# box_opener.net
KiCad netlist of a schematic drawn in EAGLE
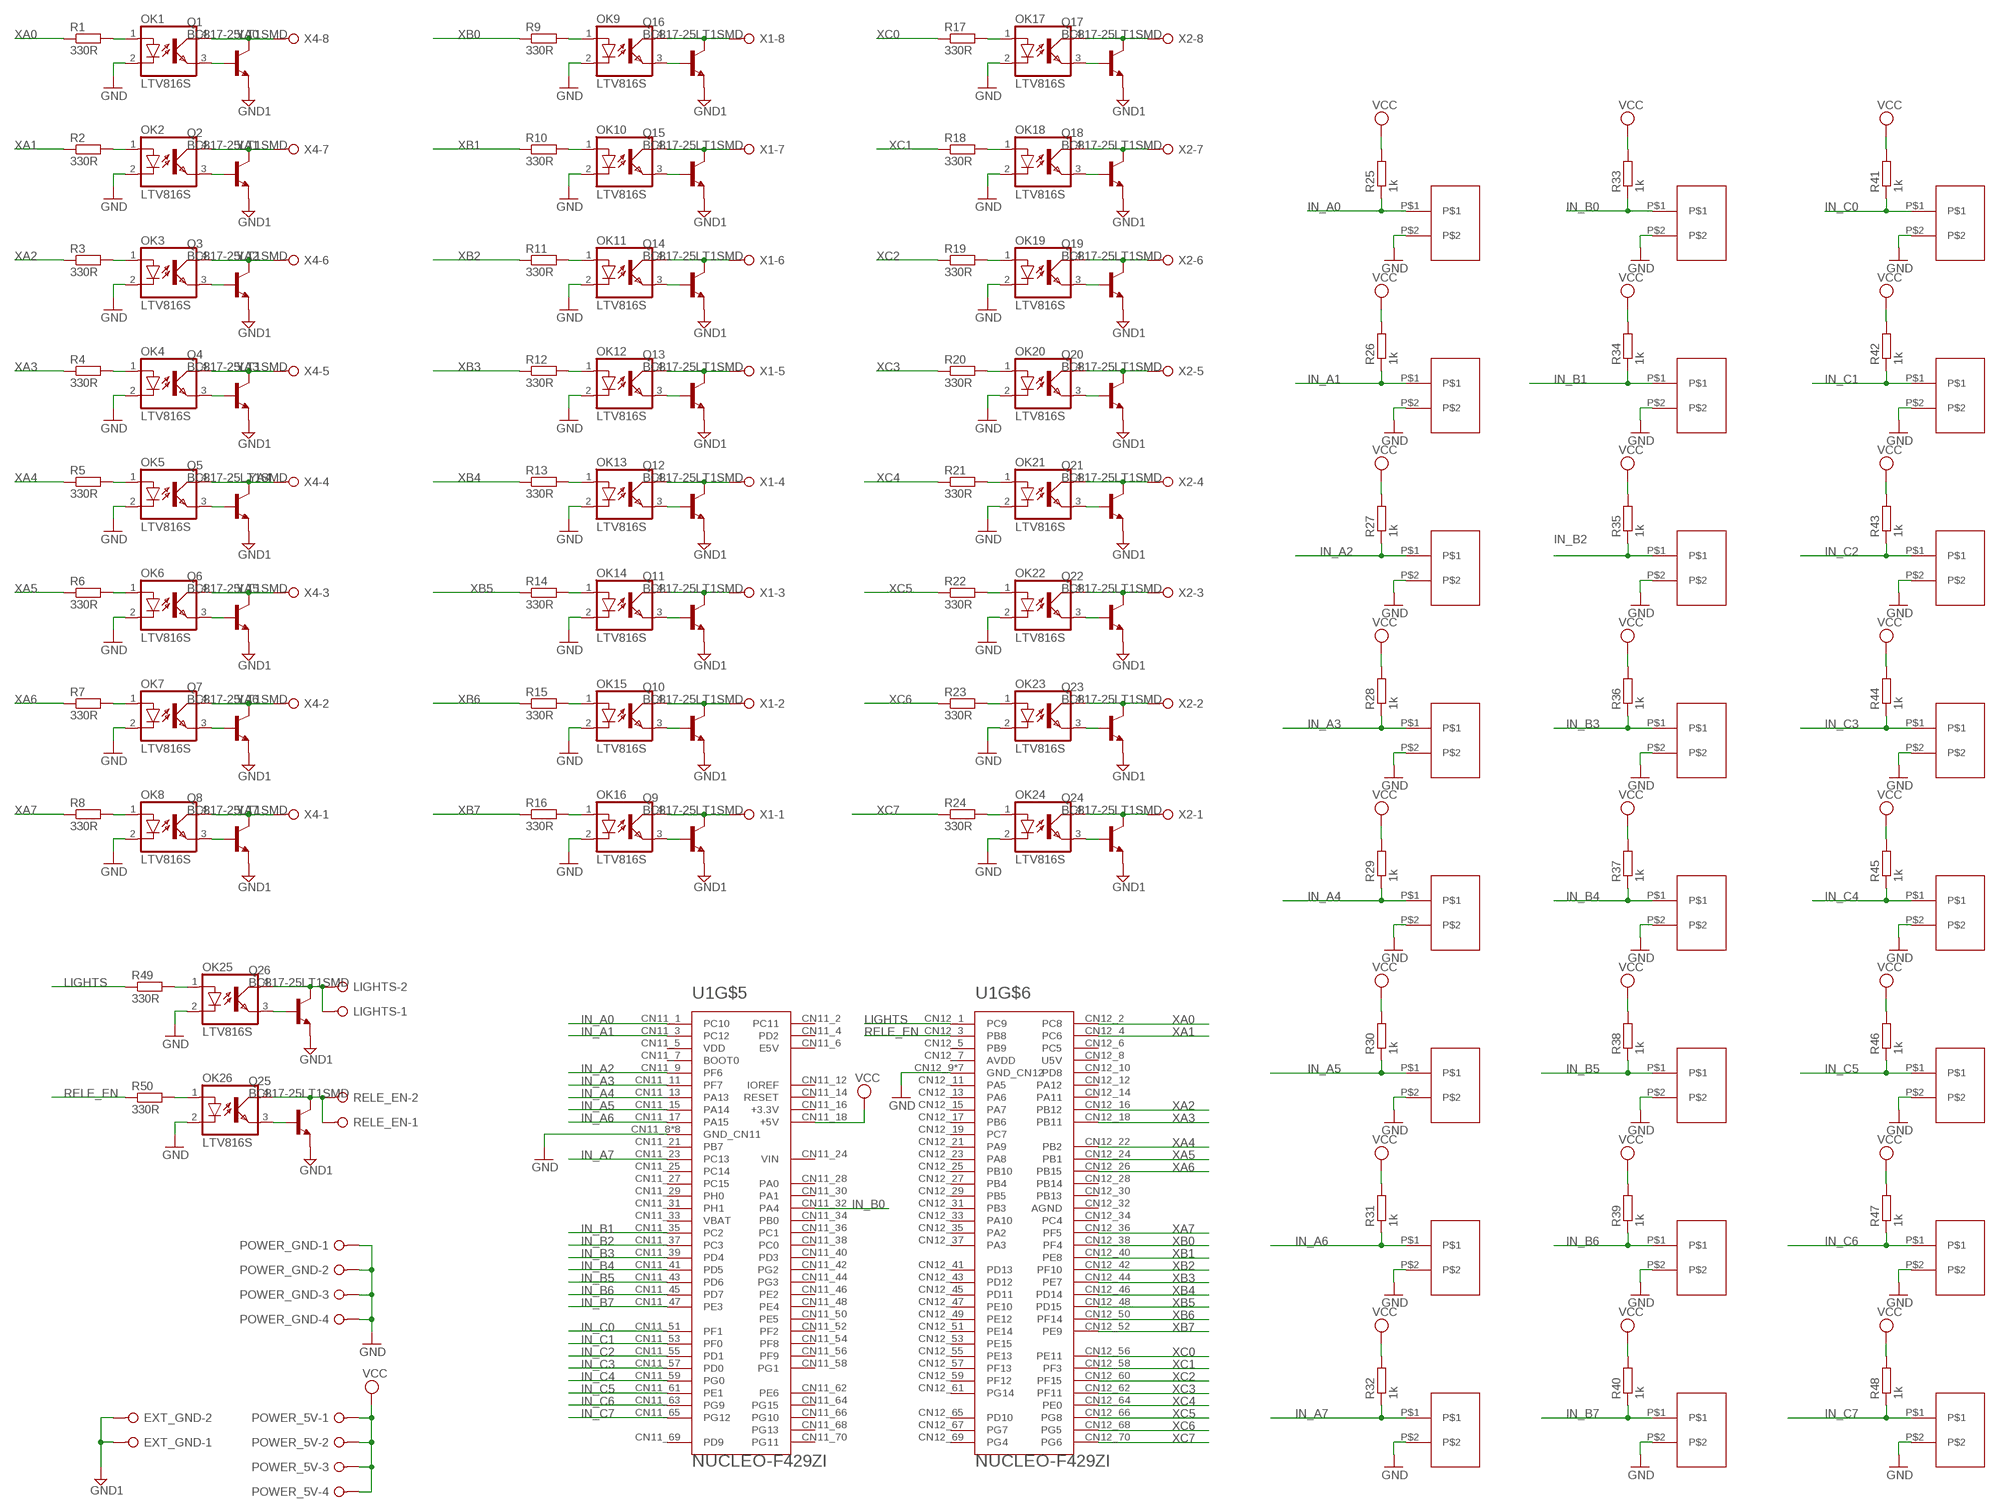
[diagram p0: schematic, sheet 1]

(export (version "E")
  (design (tool "Eeschema 10.0.6"))
  (components
    (comp (ref "EXT_GND")
      (value "W237-02P")
      (footprint "eagle-import:W237-132")
      (libsource (lib "eagle-import") (part "W237-02P"))
    )
    (comp (ref "LIGHTS")
      (value "W237-02P")
      (footprint "eagle-import:W237-132")
      (libsource (lib "eagle-import") (part "W237-02P"))
    )
    (comp (ref "OK1")
      (value "LTV816S")
      (footprint "eagle-import:DIL4-SMD")
      (libsource (lib "eagle-import") (part "LTV816S"))
    )
    (comp (ref "OK2")
      (value "LTV816S")
      (footprint "eagle-import:DIL4-SMD")
      (libsource (lib "eagle-import") (part "LTV816S"))
    )
    (comp (ref "OK3")
      (value "LTV816S")
      (footprint "eagle-import:DIL4-SMD")
      (libsource (lib "eagle-import") (part "LTV816S"))
    )
    (comp (ref "OK4")
      (value "LTV816S")
      (footprint "eagle-import:DIL4-SMD")
      (libsource (lib "eagle-import") (part "LTV816S"))
    )
    (comp (ref "OK5")
      (value "LTV816S")
      (footprint "eagle-import:DIL4-SMD")
      (libsource (lib "eagle-import") (part "LTV816S"))
    )
    (comp (ref "OK6")
      (value "LTV816S")
      (footprint "eagle-import:DIL4-SMD")
      (libsource (lib "eagle-import") (part "LTV816S"))
    )
    (comp (ref "OK7")
      (value "LTV816S")
      (footprint "eagle-import:DIL4-SMD")
      (libsource (lib "eagle-import") (part "LTV816S"))
    )
    (comp (ref "OK8")
      (value "LTV816S")
      (footprint "eagle-import:DIL4-SMD")
      (libsource (lib "eagle-import") (part "LTV816S"))
    )
    (comp (ref "OK9")
      (value "LTV816S")
      (footprint "eagle-import:DIL4-SMD")
      (libsource (lib "eagle-import") (part "LTV816S"))
    )
    (comp (ref "OK10")
      (value "LTV816S")
      (footprint "eagle-import:DIL4-SMD")
      (libsource (lib "eagle-import") (part "LTV816S"))
    )
    (comp (ref "OK11")
      (value "LTV816S")
      (footprint "eagle-import:DIL4-SMD")
      (libsource (lib "eagle-import") (part "LTV816S"))
    )
    (comp (ref "OK12")
      (value "LTV816S")
      (footprint "eagle-import:DIL4-SMD")
      (libsource (lib "eagle-import") (part "LTV816S"))
    )
    (comp (ref "OK13")
      (value "LTV816S")
      (footprint "eagle-import:DIL4-SMD")
      (libsource (lib "eagle-import") (part "LTV816S"))
    )
    (comp (ref "OK14")
      (value "LTV816S")
      (footprint "eagle-import:DIL4-SMD")
      (libsource (lib "eagle-import") (part "LTV816S"))
    )
    (comp (ref "OK15")
      (value "LTV816S")
      (footprint "eagle-import:DIL4-SMD")
      (libsource (lib "eagle-import") (part "LTV816S"))
    )
    (comp (ref "OK16")
      (value "LTV816S")
      (footprint "eagle-import:DIL4-SMD")
      (libsource (lib "eagle-import") (part "LTV816S"))
    )
    (comp (ref "OK17")
      (value "LTV816S")
      (footprint "eagle-import:DIL4-SMD")
      (libsource (lib "eagle-import") (part "LTV816S"))
    )
    (comp (ref "OK18")
      (value "LTV816S")
      (footprint "eagle-import:DIL4-SMD")
      (libsource (lib "eagle-import") (part "LTV816S"))
    )
    (comp (ref "OK19")
      (value "LTV816S")
      (footprint "eagle-import:DIL4-SMD")
      (libsource (lib "eagle-import") (part "LTV816S"))
    )
    (comp (ref "OK20")
      (value "LTV816S")
      (footprint "eagle-import:DIL4-SMD")
      (libsource (lib "eagle-import") (part "LTV816S"))
    )
    (comp (ref "OK21")
      (value "LTV816S")
      (footprint "eagle-import:DIL4-SMD")
      (libsource (lib "eagle-import") (part "LTV816S"))
    )
    (comp (ref "OK22")
      (value "LTV816S")
      (footprint "eagle-import:DIL4-SMD")
      (libsource (lib "eagle-import") (part "LTV816S"))
    )
    (comp (ref "OK23")
      (value "LTV816S")
      (footprint "eagle-import:DIL4-SMD")
      (libsource (lib "eagle-import") (part "LTV816S"))
    )
    (comp (ref "OK24")
      (value "LTV816S")
      (footprint "eagle-import:DIL4-SMD")
      (libsource (lib "eagle-import") (part "LTV816S"))
    )
    (comp (ref "OK25")
      (value "LTV816S")
      (footprint "eagle-import:DIL4-SMD")
      (libsource (lib "eagle-import") (part "LTV816S"))
    )
    (comp (ref "OK26")
      (value "LTV816S")
      (footprint "eagle-import:DIL4-SMD")
      (libsource (lib "eagle-import") (part "LTV816S"))
    )
    (comp (ref "POWER_5V")
      (value "W237-04P")
      (footprint "eagle-import:W237-4P")
      (libsource (lib "eagle-import") (part "W237-04P"))
    )
    (comp (ref "POWER_GND")
      (value "W237-04P")
      (footprint "eagle-import:W237-4P")
      (libsource (lib "eagle-import") (part "W237-04P"))
    )
    (comp (ref "Q1")
      (value "BC817-25LT1SMD")
      (footprint "eagle-import:SOT23-BEC")
      (libsource (lib "eagle-import") (part "BC817SMD-25LT1"))
    )
    (comp (ref "Q2")
      (value "BC817-25LT1SMD")
      (footprint "eagle-import:SOT23-BEC")
      (libsource (lib "eagle-import") (part "BC817SMD-25LT1"))
    )
    (comp (ref "Q3")
      (value "BC817-25LT1SMD")
      (footprint "eagle-import:SOT23-BEC")
      (libsource (lib "eagle-import") (part "BC817SMD-25LT1"))
    )
    (comp (ref "Q4")
      (value "BC817-25LT1SMD")
      (footprint "eagle-import:SOT23-BEC")
      (libsource (lib "eagle-import") (part "BC817SMD-25LT1"))
    )
    (comp (ref "Q5")
      (value "BC817-25LT1SMD")
      (footprint "eagle-import:SOT23-BEC")
      (libsource (lib "eagle-import") (part "BC817SMD-25LT1"))
    )
    (comp (ref "Q6")
      (value "BC817-25LT1SMD")
      (footprint "eagle-import:SOT23-BEC")
      (libsource (lib "eagle-import") (part "BC817SMD-25LT1"))
    )
    (comp (ref "Q7")
      (value "BC817-25LT1SMD")
      (footprint "eagle-import:SOT23-BEC")
      (libsource (lib "eagle-import") (part "BC817SMD-25LT1"))
    )
    (comp (ref "Q8")
      (value "BC817-25LT1SMD")
      (footprint "eagle-import:SOT23-BEC")
      (libsource (lib "eagle-import") (part "BC817SMD-25LT1"))
    )
    (comp (ref "Q9")
      (value "BC817-25LT1SMD")
      (footprint "eagle-import:SOT23-BEC")
      (libsource (lib "eagle-import") (part "BC817SMD-25LT1"))
    )
    (comp (ref "Q10")
      (value "BC817-25LT1SMD")
      (footprint "eagle-import:SOT23-BEC")
      (libsource (lib "eagle-import") (part "BC817SMD-25LT1"))
    )
    (comp (ref "Q11")
      (value "BC817-25LT1SMD")
      (footprint "eagle-import:SOT23-BEC")
      (libsource (lib "eagle-import") (part "BC817SMD-25LT1"))
    )
    (comp (ref "Q12")
      (value "BC817-25LT1SMD")
      (footprint "eagle-import:SOT23-BEC")
      (libsource (lib "eagle-import") (part "BC817SMD-25LT1"))
    )
    (comp (ref "Q13")
      (value "BC817-25LT1SMD")
      (footprint "eagle-import:SOT23-BEC")
      (libsource (lib "eagle-import") (part "BC817SMD-25LT1"))
    )
    (comp (ref "Q14")
      (value "BC817-25LT1SMD")
      (footprint "eagle-import:SOT23-BEC")
      (libsource (lib "eagle-import") (part "BC817SMD-25LT1"))
    )
    (comp (ref "Q15")
      (value "BC817-25LT1SMD")
      (footprint "eagle-import:SOT23-BEC")
      (libsource (lib "eagle-import") (part "BC817SMD-25LT1"))
    )
    (comp (ref "Q16")
      (value "BC817-25LT1SMD")
      (footprint "eagle-import:SOT23-BEC")
      (libsource (lib "eagle-import") (part "BC817SMD-25LT1"))
    )
    (comp (ref "Q17")
      (value "BC817-25LT1SMD")
      (footprint "eagle-import:SOT23-BEC")
      (libsource (lib "eagle-import") (part "BC817SMD-25LT1"))
    )
    (comp (ref "Q18")
      (value "BC817-25LT1SMD")
      (footprint "eagle-import:SOT23-BEC")
      (libsource (lib "eagle-import") (part "BC817SMD-25LT1"))
    )
    (comp (ref "Q19")
      (value "BC817-25LT1SMD")
      (footprint "eagle-import:SOT23-BEC")
      (libsource (lib "eagle-import") (part "BC817SMD-25LT1"))
    )
    (comp (ref "Q20")
      (value "BC817-25LT1SMD")
      (footprint "eagle-import:SOT23-BEC")
      (libsource (lib "eagle-import") (part "BC817SMD-25LT1"))
    )
    (comp (ref "Q21")
      (value "BC817-25LT1SMD")
      (footprint "eagle-import:SOT23-BEC")
      (libsource (lib "eagle-import") (part "BC817SMD-25LT1"))
    )
    (comp (ref "Q22")
      (value "BC817-25LT1SMD")
      (footprint "eagle-import:SOT23-BEC")
      (libsource (lib "eagle-import") (part "BC817SMD-25LT1"))
    )
    (comp (ref "Q23")
      (value "BC817-25LT1SMD")
      (footprint "eagle-import:SOT23-BEC")
      (libsource (lib "eagle-import") (part "BC817SMD-25LT1"))
    )
    (comp (ref "Q24")
      (value "BC817-25LT1SMD")
      (footprint "eagle-import:SOT23-BEC")
      (libsource (lib "eagle-import") (part "BC817SMD-25LT1"))
    )
    (comp (ref "Q25")
      (value "BC817-25LT1SMD")
      (footprint "eagle-import:SOT23-BEC")
      (libsource (lib "eagle-import") (part "BC817SMD-25LT1"))
    )
    (comp (ref "Q26")
      (value "BC817-25LT1SMD")
      (footprint "eagle-import:SOT23-BEC")
      (libsource (lib "eagle-import") (part "BC817SMD-25LT1"))
    )
    (comp (ref "R1")
      (value "330R")
      (footprint "eagle-import:M1206")
      (libsource (lib "eagle-import") (part "R-EU_M1206"))
    )
    (comp (ref "R2")
      (value "330R")
      (footprint "eagle-import:M1206")
      (libsource (lib "eagle-import") (part "R-EU_M1206"))
    )
    (comp (ref "R3")
      (value "330R")
      (footprint "eagle-import:M1206")
      (libsource (lib "eagle-import") (part "R-EU_M1206"))
    )
    (comp (ref "R4")
      (value "330R")
      (footprint "eagle-import:M1206")
      (libsource (lib "eagle-import") (part "R-EU_M1206"))
    )
    (comp (ref "R5")
      (value "330R")
      (footprint "eagle-import:M1206")
      (libsource (lib "eagle-import") (part "R-EU_M1206"))
    )
    (comp (ref "R6")
      (value "330R")
      (footprint "eagle-import:M1206")
      (libsource (lib "eagle-import") (part "R-EU_M1206"))
    )
    (comp (ref "R7")
      (value "330R")
      (footprint "eagle-import:M1206")
      (libsource (lib "eagle-import") (part "R-EU_M1206"))
    )
    (comp (ref "R8")
      (value "330R")
      (footprint "eagle-import:M1206")
      (libsource (lib "eagle-import") (part "R-EU_M1206"))
    )
    (comp (ref "R9")
      (value "330R")
      (footprint "eagle-import:M1206")
      (libsource (lib "eagle-import") (part "R-EU_M1206"))
    )
    (comp (ref "R10")
      (value "330R")
      (footprint "eagle-import:M1206")
      (libsource (lib "eagle-import") (part "R-EU_M1206"))
    )
    (comp (ref "R11")
      (value "330R")
      (footprint "eagle-import:M1206")
      (libsource (lib "eagle-import") (part "R-EU_M1206"))
    )
    (comp (ref "R12")
      (value "330R")
      (footprint "eagle-import:M1206")
      (libsource (lib "eagle-import") (part "R-EU_M1206"))
    )
    (comp (ref "R13")
      (value "330R")
      (footprint "eagle-import:M1206")
      (libsource (lib "eagle-import") (part "R-EU_M1206"))
    )
    (comp (ref "R14")
      (value "330R")
      (footprint "eagle-import:M1206")
      (libsource (lib "eagle-import") (part "R-EU_M1206"))
    )
    (comp (ref "R15")
      (value "330R")
      (footprint "eagle-import:M1206")
      (libsource (lib "eagle-import") (part "R-EU_M1206"))
    )
    (comp (ref "R16")
      (value "330R")
      (footprint "eagle-import:M1206")
      (libsource (lib "eagle-import") (part "R-EU_M1206"))
    )
    (comp (ref "R17")
      (value "330R")
      (footprint "eagle-import:M1206")
      (libsource (lib "eagle-import") (part "R-EU_M1206"))
    )
    (comp (ref "R18")
      (value "330R")
      (footprint "eagle-import:M1206")
      (libsource (lib "eagle-import") (part "R-EU_M1206"))
    )
    (comp (ref "R19")
      (value "330R")
      (footprint "eagle-import:M1206")
      (libsource (lib "eagle-import") (part "R-EU_M1206"))
    )
    (comp (ref "R20")
      (value "330R")
      (footprint "eagle-import:M1206")
      (libsource (lib "eagle-import") (part "R-EU_M1206"))
    )
    (comp (ref "R21")
      (value "330R")
      (footprint "eagle-import:M1206")
      (libsource (lib "eagle-import") (part "R-EU_M1206"))
    )
    (comp (ref "R22")
      (value "330R")
      (footprint "eagle-import:M1206")
      (libsource (lib "eagle-import") (part "R-EU_M1206"))
    )
    (comp (ref "R23")
      (value "330R")
      (footprint "eagle-import:M1206")
      (libsource (lib "eagle-import") (part "R-EU_M1206"))
    )
    (comp (ref "R24")
      (value "330R")
      (footprint "eagle-import:M1206")
      (libsource (lib "eagle-import") (part "R-EU_M1206"))
    )
    (comp (ref "R25")
      (value "1k")
      (footprint "eagle-import:M1206")
      (libsource (lib "eagle-import") (part "R-EU_M1206"))
    )
    (comp (ref "R26")
      (value "1k")
      (footprint "eagle-import:M1206")
      (libsource (lib "eagle-import") (part "R-EU_M1206"))
    )
    (comp (ref "R27")
      (value "1k")
      (footprint "eagle-import:M1206")
      (libsource (lib "eagle-import") (part "R-EU_M1206"))
    )
    (comp (ref "R28")
      (value "1k")
      (footprint "eagle-import:M1206")
      (libsource (lib "eagle-import") (part "R-EU_M1206"))
    )
    (comp (ref "R29")
      (value "1k")
      (footprint "eagle-import:M1206")
      (libsource (lib "eagle-import") (part "R-EU_M1206"))
    )
    (comp (ref "R30")
      (value "1k")
      (footprint "eagle-import:M1206")
      (libsource (lib "eagle-import") (part "R-EU_M1206"))
    )
    (comp (ref "R31")
      (value "1k")
      (footprint "eagle-import:M1206")
      (libsource (lib "eagle-import") (part "R-EU_M1206"))
    )
    (comp (ref "R32")
      (value "1k")
      (footprint "eagle-import:M1206")
      (libsource (lib "eagle-import") (part "R-EU_M1206"))
    )
    (comp (ref "R33")
      (value "1k")
      (footprint "eagle-import:M1206")
      (libsource (lib "eagle-import") (part "R-EU_M1206"))
    )
    (comp (ref "R34")
      (value "1k")
      (footprint "eagle-import:M1206")
      (libsource (lib "eagle-import") (part "R-EU_M1206"))
    )
    (comp (ref "R35")
      (value "1k")
      (footprint "eagle-import:M1206")
      (libsource (lib "eagle-import") (part "R-EU_M1206"))
    )
    (comp (ref "R36")
      (value "1k")
      (footprint "eagle-import:M1206")
      (libsource (lib "eagle-import") (part "R-EU_M1206"))
    )
    (comp (ref "R37")
      (value "1k")
      (footprint "eagle-import:M1206")
      (libsource (lib "eagle-import") (part "R-EU_M1206"))
    )
    (comp (ref "R38")
      (value "1k")
      (footprint "eagle-import:M1206")
      (libsource (lib "eagle-import") (part "R-EU_M1206"))
    )
    (comp (ref "R39")
      (value "1k")
      (footprint "eagle-import:M1206")
      (libsource (lib "eagle-import") (part "R-EU_M1206"))
    )
    (comp (ref "R40")
      (value "1k")
      (footprint "eagle-import:M1206")
      (libsource (lib "eagle-import") (part "R-EU_M1206"))
    )
    (comp (ref "R41")
      (value "1k")
      (footprint "eagle-import:M1206")
      (libsource (lib "eagle-import") (part "R-EU_M1206"))
    )
    (comp (ref "R42")
      (value "1k")
      (footprint "eagle-import:M1206")
      (libsource (lib "eagle-import") (part "R-EU_M1206"))
    )
    (comp (ref "R43")
      (value "1k")
      (footprint "eagle-import:M1206")
      (libsource (lib "eagle-import") (part "R-EU_M1206"))
    )
    (comp (ref "R44")
      (value "1k")
      (footprint "eagle-import:M1206")
      (libsource (lib "eagle-import") (part "R-EU_M1206"))
    )
    (comp (ref "R45")
      (value "1k")
      (footprint "eagle-import:M1206")
      (libsource (lib "eagle-import") (part "R-EU_M1206"))
    )
    (comp (ref "R46")
      (value "1k")
      (footprint "eagle-import:M1206")
      (libsource (lib "eagle-import") (part "R-EU_M1206"))
    )
    (comp (ref "R47")
      (value "1k")
      (footprint "eagle-import:M1206")
      (libsource (lib "eagle-import") (part "R-EU_M1206"))
    )
    (comp (ref "R48")
      (value "1k")
      (footprint "eagle-import:M1206")
      (libsource (lib "eagle-import") (part "R-EU_M1206"))
    )
    (comp (ref "R49")
      (value "330R")
      (footprint "eagle-import:M1206")
      (libsource (lib "eagle-import") (part "R-EU_M1206"))
    )
    (comp (ref "R50")
      (value "330R")
      (footprint "eagle-import:M1206")
      (libsource (lib "eagle-import") (part "R-EU_M1206"))
    )
    (comp (ref "RELE_EN")
      (value "W237-02P")
      (footprint "eagle-import:W237-132")
      (libsource (lib "eagle-import") (part "W237-02P"))
    )
    (comp (ref "U$1")
      (value "PSH04-02")
      (footprint "eagle-import:PSH04-02")
      (libsource (lib "eagle-import") (part "PSH04-02"))
    )
    (comp (ref "U$2")
      (value "PSH04-02")
      (footprint "eagle-import:PSH04-02")
      (libsource (lib "eagle-import") (part "PSH04-02"))
    )
    (comp (ref "U$3")
      (value "PSH04-02")
      (footprint "eagle-import:PSH04-02")
      (libsource (lib "eagle-import") (part "PSH04-02"))
    )
    (comp (ref "U$4")
      (value "PSH04-02")
      (footprint "eagle-import:PSH04-02")
      (libsource (lib "eagle-import") (part "PSH04-02"))
    )
    (comp (ref "U$5")
      (value "PSH04-02")
      (footprint "eagle-import:PSH04-02")
      (libsource (lib "eagle-import") (part "PSH04-02"))
    )
    (comp (ref "U$6")
      (value "PSH04-02")
      (footprint "eagle-import:PSH04-02")
      (libsource (lib "eagle-import") (part "PSH04-02"))
    )
    (comp (ref "U$7")
      (value "PSH04-02")
      (footprint "eagle-import:PSH04-02")
      (libsource (lib "eagle-import") (part "PSH04-02"))
    )
    (comp (ref "U$8")
      (value "PSH04-02")
      (footprint "eagle-import:PSH04-02")
      (libsource (lib "eagle-import") (part "PSH04-02"))
    )
    (comp (ref "U$9")
      (value "PSH04-02")
      (footprint "eagle-import:PSH04-02")
      (libsource (lib "eagle-import") (part "PSH04-02"))
    )
    (comp (ref "U$10")
      (value "PSH04-02")
      (footprint "eagle-import:PSH04-02")
      (libsource (lib "eagle-import") (part "PSH04-02"))
    )
    (comp (ref "U$11")
      (value "PSH04-02")
      (footprint "eagle-import:PSH04-02")
      (libsource (lib "eagle-import") (part "PSH04-02"))
    )
    (comp (ref "U$12")
      (value "PSH04-02")
      (footprint "eagle-import:PSH04-02")
      (libsource (lib "eagle-import") (part "PSH04-02"))
    )
    (comp (ref "U$13")
      (value "PSH04-02")
      (footprint "eagle-import:PSH04-02")
      (libsource (lib "eagle-import") (part "PSH04-02"))
    )
    (comp (ref "U$14")
      (value "PSH04-02")
      (footprint "eagle-import:PSH04-02")
      (libsource (lib "eagle-import") (part "PSH04-02"))
    )
    (comp (ref "U$15")
      (value "PSH04-02")
      (footprint "eagle-import:PSH04-02")
      (libsource (lib "eagle-import") (part "PSH04-02"))
    )
    (comp (ref "U$16")
      (value "PSH04-02")
      (footprint "eagle-import:PSH04-02")
      (libsource (lib "eagle-import") (part "PSH04-02"))
    )
    (comp (ref "U$17")
      (value "PSH04-02")
      (footprint "eagle-import:PSH04-02")
      (libsource (lib "eagle-import") (part "PSH04-02"))
    )
    (comp (ref "U$18")
      (value "PSH04-02")
      (footprint "eagle-import:PSH04-02")
      (libsource (lib "eagle-import") (part "PSH04-02"))
    )
    (comp (ref "U$19")
      (value "PSH04-02")
      (footprint "eagle-import:PSH04-02")
      (libsource (lib "eagle-import") (part "PSH04-02"))
    )
    (comp (ref "U$20")
      (value "PSH04-02")
      (footprint "eagle-import:PSH04-02")
      (libsource (lib "eagle-import") (part "PSH04-02"))
    )
    (comp (ref "U$21")
      (value "PSH04-02")
      (footprint "eagle-import:PSH04-02")
      (libsource (lib "eagle-import") (part "PSH04-02"))
    )
    (comp (ref "U$22")
      (value "PSH04-02")
      (footprint "eagle-import:PSH04-02")
      (libsource (lib "eagle-import") (part "PSH04-02"))
    )
    (comp (ref "U$23")
      (value "PSH04-02")
      (footprint "eagle-import:PSH04-02")
      (libsource (lib "eagle-import") (part "PSH04-02"))
    )
    (comp (ref "U$24")
      (value "PSH04-02")
      (footprint "eagle-import:PSH04-02")
      (libsource (lib "eagle-import") (part "PSH04-02"))
    )
    (comp (ref "U1")
      (value "NUCLEO-F429ZI")
      (footprint "eagle-import:MODULE_NUCLEO-F429ZI")
      (fields (field (name "DIGI-KEY_PART_NUMBER") "497-16280-ND") (field (name "MF") "STMicroelectronics"))
      (libsource (lib "eagle-import") (part "NUCLEO-F429ZI"))
    )
    (comp (ref "X1")
      (value "W237-08P")
      (footprint "eagle-import:W237-8P")
      (libsource (lib "eagle-import") (part "W237-08P"))
    )
    (comp (ref "X2")
      (value "W237-08P")
      (footprint "eagle-import:W237-8P")
      (libsource (lib "eagle-import") (part "W237-08P"))
    )
    (comp (ref "X4")
      (value "W237-08P")
      (footprint "eagle-import:W237-8P")
      (libsource (lib "eagle-import") (part "W237-08P"))
    )
  )
  (nets
    (net (code "1") (name "/IN_A0") (class "Default")
      (node (ref "R25") (pin "1") (pinfunction "1_1") (pintype "passive"))
      (node (ref "U$1") (pin "P$1") (pinfunction "P$1_P$1") (pintype "bidirectional"))
      (node (ref "U1") (pin "CN11_1") (pinfunction "PC10_CN11_1") (pintype "passive"))
    )
    (net (code "2") (name "/IN_A1") (class "Default")
      (node (ref "R26") (pin "1") (pinfunction "1_1") (pintype "passive"))
      (node (ref "U$2") (pin "P$1") (pinfunction "P$1_P$1") (pintype "bidirectional"))
      (node (ref "U1") (pin "CN11_3") (pinfunction "PC12_CN11_3") (pintype "passive"))
    )
    (net (code "3") (name "/IN_A2") (class "Default")
      (node (ref "R27") (pin "1") (pinfunction "1_1") (pintype "passive"))
      (node (ref "U$3") (pin "P$1") (pinfunction "P$1_P$1") (pintype "bidirectional"))
      (node (ref "U1") (pin "CN11_9") (pinfunction "PF6_CN11_9") (pintype "passive"))
    )
    (net (code "4") (name "/IN_A3") (class "Default")
      (node (ref "R28") (pin "1") (pinfunction "1_1") (pintype "passive"))
      (node (ref "U$4") (pin "P$1") (pinfunction "P$1_P$1") (pintype "bidirectional"))
      (node (ref "U1") (pin "CN11_11") (pinfunction "PF7_CN11_11") (pintype "passive"))
    )
    (net (code "5") (name "/IN_A4") (class "Default")
      (node (ref "R29") (pin "1") (pinfunction "1_1") (pintype "passive"))
      (node (ref "U$5") (pin "P$1") (pinfunction "P$1_P$1") (pintype "bidirectional"))
      (node (ref "U1") (pin "CN11_13") (pinfunction "PA13_CN11_13") (pintype "passive"))
    )
    (net (code "6") (name "/IN_A5") (class "Default")
      (node (ref "R30") (pin "1") (pinfunction "1_1") (pintype "passive"))
      (node (ref "U$6") (pin "P$1") (pinfunction "P$1_P$1") (pintype "bidirectional"))
      (node (ref "U1") (pin "CN11_15") (pinfunction "PA14_CN11_15") (pintype "passive"))
    )
    (net (code "7") (name "/IN_A6") (class "Default")
      (node (ref "R31") (pin "1") (pinfunction "1_1") (pintype "passive"))
      (node (ref "U$7") (pin "P$1") (pinfunction "P$1_P$1") (pintype "bidirectional"))
      (node (ref "U1") (pin "CN11_17") (pinfunction "PA15_CN11_17") (pintype "passive"))
    )
    (net (code "8") (name "/IN_A7") (class "Default")
      (node (ref "R32") (pin "1") (pinfunction "1_1") (pintype "passive"))
      (node (ref "U$8") (pin "P$1") (pinfunction "P$1_P$1") (pintype "bidirectional"))
      (node (ref "U1") (pin "CN11_23") (pinfunction "PC13_CN11_23") (pintype "passive"))
    )
    (net (code "9") (name "/IN_B0") (class "Default")
      (node (ref "R33") (pin "1") (pinfunction "1_1") (pintype "passive"))
      (node (ref "U$9") (pin "P$1") (pinfunction "P$1_P$1") (pintype "bidirectional"))
      (node (ref "U1") (pin "CN11_32") (pinfunction "PA4_CN11_32") (pintype "passive"))
    )
    (net (code "10") (name "/IN_B1") (class "Default")
      (node (ref "R34") (pin "1") (pinfunction "1_1") (pintype "passive"))
      (node (ref "U$10") (pin "P$1") (pinfunction "P$1_P$1") (pintype "bidirectional"))
      (node (ref "U1") (pin "CN11_35") (pinfunction "PC2_CN11_35") (pintype "passive"))
    )
    (net (code "11") (name "/IN_B2") (class "Default")
      (node (ref "R35") (pin "1") (pinfunction "1_1") (pintype "passive"))
      (node (ref "U$11") (pin "P$1") (pinfunction "P$1_P$1") (pintype "bidirectional"))
      (node (ref "U1") (pin "CN11_37") (pinfunction "PC3_CN11_37") (pintype "passive"))
    )
    (net (code "12") (name "/IN_B3") (class "Default")
      (node (ref "R36") (pin "1") (pinfunction "1_1") (pintype "passive"))
      (node (ref "U$12") (pin "P$1") (pinfunction "P$1_P$1") (pintype "bidirectional"))
      (node (ref "U1") (pin "CN11_39") (pinfunction "PD4_CN11_39") (pintype "passive"))
    )
    (net (code "13") (name "/IN_B4") (class "Default")
      (node (ref "R37") (pin "1") (pinfunction "1_1") (pintype "passive"))
      (node (ref "U$13") (pin "P$1") (pinfunction "P$1_P$1") (pintype "bidirectional"))
      (node (ref "U1") (pin "CN11_41") (pinfunction "PD5_CN11_41") (pintype "passive"))
    )
    (net (code "14") (name "/IN_B5") (class "Default")
      (node (ref "R38") (pin "1") (pinfunction "1_1") (pintype "passive"))
      (node (ref "U$14") (pin "P$1") (pinfunction "P$1_P$1") (pintype "bidirectional"))
      (node (ref "U1") (pin "CN11_43") (pinfunction "PD6_CN11_43") (pintype "passive"))
    )
    (net (code "15") (name "/IN_B6") (class "Default")
      (node (ref "R39") (pin "1") (pinfunction "1_1") (pintype "passive"))
      (node (ref "U$15") (pin "P$1") (pinfunction "P$1_P$1") (pintype "bidirectional"))
      (node (ref "U1") (pin "CN11_45") (pinfunction "PD7_CN11_45") (pintype "passive"))
    )
    (net (code "16") (name "/IN_B7") (class "Default")
      (node (ref "R40") (pin "1") (pinfunction "1_1") (pintype "passive"))
      (node (ref "U$16") (pin "P$1") (pinfunction "P$1_P$1") (pintype "bidirectional"))
      (node (ref "U1") (pin "CN11_47") (pinfunction "PE3_CN11_47") (pintype "passive"))
    )
    (net (code "17") (name "/IN_C0") (class "Default")
      (node (ref "R41") (pin "1") (pinfunction "1_1") (pintype "passive"))
      (node (ref "U$17") (pin "P$1") (pinfunction "P$1_P$1") (pintype "bidirectional"))
      (node (ref "U1") (pin "CN11_51") (pinfunction "PF1_CN11_51") (pintype "passive"))
    )
    (net (code "18") (name "/IN_C1") (class "Default")
      (node (ref "R42") (pin "1") (pinfunction "1_1") (pintype "passive"))
      (node (ref "U$18") (pin "P$1") (pinfunction "P$1_P$1") (pintype "bidirectional"))
      (node (ref "U1") (pin "CN11_53") (pinfunction "PF0_CN11_53") (pintype "passive"))
    )
    (net (code "19") (name "/IN_C2") (class "Default")
      (node (ref "R43") (pin "1") (pinfunction "1_1") (pintype "passive"))
      (node (ref "U$19") (pin "P$1") (pinfunction "P$1_P$1") (pintype "bidirectional"))
      (node (ref "U1") (pin "CN11_55") (pinfunction "PD1_CN11_55") (pintype "passive"))
    )
    (net (code "20") (name "/IN_C3") (class "Default")
      (node (ref "R44") (pin "1") (pinfunction "1_1") (pintype "passive"))
      (node (ref "U$20") (pin "P$1") (pinfunction "P$1_P$1") (pintype "bidirectional"))
      (node (ref "U1") (pin "CN11_57") (pinfunction "PD0_CN11_57") (pintype "passive"))
    )
    (net (code "21") (name "/IN_C4") (class "Default")
      (node (ref "R45") (pin "1") (pinfunction "1_1") (pintype "passive"))
      (node (ref "U$21") (pin "P$1") (pinfunction "P$1_P$1") (pintype "bidirectional"))
      (node (ref "U1") (pin "CN11_59") (pinfunction "PG0_CN11_59") (pintype "passive"))
    )
    (net (code "22") (name "/IN_C5") (class "Default")
      (node (ref "R46") (pin "1") (pinfunction "1_1") (pintype "passive"))
      (node (ref "U$22") (pin "P$1") (pinfunction "P$1_P$1") (pintype "bidirectional"))
      (node (ref "U1") (pin "CN11_61") (pinfunction "PE1_CN11_61") (pintype "passive"))
    )
    (net (code "23") (name "/IN_C6") (class "Default")
      (node (ref "R47") (pin "1") (pinfunction "1_1") (pintype "passive"))
      (node (ref "U$23") (pin "P$1") (pinfunction "P$1_P$1") (pintype "bidirectional"))
      (node (ref "U1") (pin "CN11_63") (pinfunction "PG9_CN11_63") (pintype "passive"))
    )
    (net (code "24") (name "/IN_C7") (class "Default")
      (node (ref "R48") (pin "1") (pinfunction "1_1") (pintype "passive"))
      (node (ref "U$24") (pin "P$1") (pinfunction "P$1_P$1") (pintype "bidirectional"))
      (node (ref "U1") (pin "CN11_65") (pinfunction "PG12_CN11_65") (pintype "passive"))
    )
    (net (code "25") (name "/LIGHTS") (class "Default")
      (node (ref "R49") (pin "1") (pinfunction "1_1") (pintype "passive"))
      (node (ref "U1") (pin "CN12_1") (pinfunction "PC9_CN12_1") (pintype "passive"))
    )
    (net (code "26") (name "/RELE_EN") (class "Default")
      (node (ref "R50") (pin "1") (pinfunction "1_1") (pintype "passive"))
      (node (ref "U1") (pin "CN12_3") (pinfunction "PB8_CN12_3") (pintype "passive"))
    )
    (net (code "27") (name "/XA0") (class "Default")
      (node (ref "R1") (pin "1") (pinfunction "1_1") (pintype "passive"))
      (node (ref "U1") (pin "CN12_2") (pinfunction "PC8_CN12_2") (pintype "passive"))
    )
    (net (code "28") (name "/XA1") (class "Default")
      (node (ref "R2") (pin "1") (pinfunction "1_1") (pintype "passive"))
      (node (ref "U1") (pin "CN12_4") (pinfunction "PC6_CN12_4") (pintype "passive"))
    )
    (net (code "29") (name "/XA2") (class "Default")
      (node (ref "R3") (pin "1") (pinfunction "1_1") (pintype "passive"))
      (node (ref "U1") (pin "CN12_16") (pinfunction "PB12_CN12_16") (pintype "passive"))
    )
    (net (code "30") (name "/XA3") (class "Default")
      (node (ref "R4") (pin "1") (pinfunction "1_1") (pintype "passive"))
      (node (ref "U1") (pin "CN12_18") (pinfunction "PB11_CN12_18") (pintype "passive"))
    )
    (net (code "31") (name "/XA4") (class "Default")
      (node (ref "R5") (pin "1") (pinfunction "1_1") (pintype "passive"))
      (node (ref "U1") (pin "CN12_22") (pinfunction "PB2_CN12_22") (pintype "passive"))
    )
    (net (code "32") (name "/XA5") (class "Default")
      (node (ref "R6") (pin "1") (pinfunction "1_1") (pintype "passive"))
      (node (ref "U1") (pin "CN12_24") (pinfunction "PB1_CN12_24") (pintype "passive"))
    )
    (net (code "33") (name "/XA6") (class "Default")
      (node (ref "R7") (pin "1") (pinfunction "1_1") (pintype "passive"))
      (node (ref "U1") (pin "CN12_26") (pinfunction "PB15_CN12_26") (pintype "passive"))
    )
    (net (code "34") (name "/XA7") (class "Default")
      (node (ref "R8") (pin "1") (pinfunction "1_1") (pintype "passive"))
      (node (ref "U1") (pin "CN12_36") (pinfunction "PF5_CN12_36") (pintype "passive"))
    )
    (net (code "35") (name "/XB0") (class "Default")
      (node (ref "R9") (pin "1") (pinfunction "1_1") (pintype "passive"))
      (node (ref "U1") (pin "CN12_38") (pinfunction "PF4_CN12_38") (pintype "passive"))
    )
    (net (code "36") (name "/XB1") (class "Default")
      (node (ref "R10") (pin "1") (pinfunction "1_1") (pintype "passive"))
      (node (ref "U1") (pin "CN12_40") (pinfunction "PE8_CN12_40") (pintype "passive"))
    )
    (net (code "37") (name "/XB2") (class "Default")
      (node (ref "R11") (pin "1") (pinfunction "1_1") (pintype "passive"))
      (node (ref "U1") (pin "CN12_42") (pinfunction "PF10_CN12_42") (pintype "passive"))
    )
    (net (code "38") (name "/XB3") (class "Default")
      (node (ref "R12") (pin "1") (pinfunction "1_1") (pintype "passive"))
      (node (ref "U1") (pin "CN12_44") (pinfunction "PE7_CN12_44") (pintype "passive"))
    )
    (net (code "39") (name "/XB4") (class "Default")
      (node (ref "R13") (pin "1") (pinfunction "1_1") (pintype "passive"))
      (node (ref "U1") (pin "CN12_46") (pinfunction "PD14_CN12_46") (pintype "passive"))
    )
    (net (code "40") (name "/XB5") (class "Default")
      (node (ref "R14") (pin "1") (pinfunction "1_1") (pintype "passive"))
      (node (ref "U1") (pin "CN12_48") (pinfunction "PD15_CN12_48") (pintype "passive"))
    )
    (net (code "41") (name "/XB6") (class "Default")
      (node (ref "R15") (pin "1") (pinfunction "1_1") (pintype "passive"))
      (node (ref "U1") (pin "CN12_50") (pinfunction "PF14_CN12_50") (pintype "passive"))
    )
    (net (code "42") (name "/XB7") (class "Default")
      (node (ref "R16") (pin "1") (pinfunction "1_1") (pintype "passive"))
      (node (ref "U1") (pin "CN12_52") (pinfunction "PE9_CN12_52") (pintype "passive"))
    )
    (net (code "43") (name "/XC0") (class "Default")
      (node (ref "R17") (pin "1") (pinfunction "1_1") (pintype "passive"))
      (node (ref "U1") (pin "CN12_56") (pinfunction "PE11_CN12_56") (pintype "passive"))
    )
    (net (code "44") (name "/XC1") (class "Default")
      (node (ref "R18") (pin "1") (pinfunction "1_1") (pintype "passive"))
      (node (ref "U1") (pin "CN12_58") (pinfunction "PF3_CN12_58") (pintype "passive"))
    )
    (net (code "45") (name "/XC2") (class "Default")
      (node (ref "R19") (pin "1") (pinfunction "1_1") (pintype "passive"))
      (node (ref "U1") (pin "CN12_60") (pinfunction "PF15_CN12_60") (pintype "passive"))
    )
    (net (code "46") (name "/XC3") (class "Default")
      (node (ref "R20") (pin "1") (pinfunction "1_1") (pintype "passive"))
      (node (ref "U1") (pin "CN12_62") (pinfunction "PF11_CN12_62") (pintype "passive"))
    )
    (net (code "47") (name "/XC4") (class "Default")
      (node (ref "R21") (pin "1") (pinfunction "1_1") (pintype "passive"))
      (node (ref "U1") (pin "CN12_64") (pinfunction "PE0_CN12_64") (pintype "passive"))
    )
    (net (code "48") (name "/XC5") (class "Default")
      (node (ref "R22") (pin "1") (pinfunction "1_1") (pintype "passive"))
      (node (ref "U1") (pin "CN12_66") (pinfunction "PG8_CN12_66") (pintype "passive"))
    )
    (net (code "49") (name "/XC6") (class "Default")
      (node (ref "R23") (pin "1") (pinfunction "1_1") (pintype "passive"))
      (node (ref "U1") (pin "CN12_68") (pinfunction "PG5_CN12_68") (pintype "passive"))
    )
    (net (code "50") (name "/XC7") (class "Default")
      (node (ref "R24") (pin "1") (pinfunction "1_1") (pintype "passive"))
      (node (ref "U1") (pin "CN12_70") (pinfunction "PG6_CN12_70") (pintype "passive"))
    )
    (net (code "51") (name "/YA0") (class "Default")
      (node (ref "OK1") (pin "4") (pinfunction "COL_4") (pintype "passive"))
      (node (ref "Q1") (pin "C") (pinfunction "C_C") (pintype "passive"))
      (node (ref "X4") (pin "8") (pinfunction "KL_8") (pintype "passive"))
    )
    (net (code "52") (name "/YA1") (class "Default")
      (node (ref "OK2") (pin "4") (pinfunction "COL_4") (pintype "passive"))
      (node (ref "Q2") (pin "C") (pinfunction "C_C") (pintype "passive"))
      (node (ref "X4") (pin "7") (pinfunction "KL_7") (pintype "passive"))
    )
    (net (code "53") (name "/YA2") (class "Default")
      (node (ref "OK3") (pin "4") (pinfunction "COL_4") (pintype "passive"))
      (node (ref "Q3") (pin "C") (pinfunction "C_C") (pintype "passive"))
      (node (ref "X4") (pin "6") (pinfunction "KL_6") (pintype "passive"))
    )
    (net (code "54") (name "/YA3") (class "Default")
      (node (ref "OK4") (pin "4") (pinfunction "COL_4") (pintype "passive"))
      (node (ref "Q4") (pin "C") (pinfunction "C_C") (pintype "passive"))
      (node (ref "X4") (pin "5") (pinfunction "KL_5") (pintype "passive"))
    )
    (net (code "55") (name "/YA4") (class "Default")
      (node (ref "OK5") (pin "4") (pinfunction "COL_4") (pintype "passive"))
      (node (ref "Q5") (pin "C") (pinfunction "C_C") (pintype "passive"))
      (node (ref "X4") (pin "4") (pinfunction "KL_4") (pintype "passive"))
    )
    (net (code "56") (name "/YA5") (class "Default")
      (node (ref "OK6") (pin "4") (pinfunction "COL_4") (pintype "passive"))
      (node (ref "Q6") (pin "C") (pinfunction "C_C") (pintype "passive"))
      (node (ref "X4") (pin "3") (pinfunction "KL_3") (pintype "passive"))
    )
    (net (code "57") (name "/YA6") (class "Default")
      (node (ref "OK7") (pin "4") (pinfunction "COL_4") (pintype "passive"))
      (node (ref "Q7") (pin "C") (pinfunction "C_C") (pintype "passive"))
      (node (ref "X4") (pin "2") (pinfunction "KL_2") (pintype "passive"))
    )
    (net (code "58") (name "/YA7") (class "Default")
      (node (ref "OK8") (pin "4") (pinfunction "COL_4") (pintype "passive"))
      (node (ref "Q8") (pin "C") (pinfunction "C_C") (pintype "passive"))
      (node (ref "X4") (pin "1") (pinfunction "KL_1") (pintype "passive"))
    )
    (net (code "59") (name "GND") (class "Default")
      (node (ref "OK1") (pin "2") (pinfunction "C_2") (pintype "passive"))
      (node (ref "OK10") (pin "2") (pinfunction "C_2") (pintype "passive"))
      (node (ref "OK11") (pin "2") (pinfunction "C_2") (pintype "passive"))
      (node (ref "OK12") (pin "2") (pinfunction "C_2") (pintype "passive"))
      (node (ref "OK13") (pin "2") (pinfunction "C_2") (pintype "passive"))
      (node (ref "OK14") (pin "2") (pinfunction "C_2") (pintype "passive"))
      (node (ref "OK15") (pin "2") (pinfunction "C_2") (pintype "passive"))
      (node (ref "OK16") (pin "2") (pinfunction "C_2") (pintype "passive"))
      (node (ref "OK17") (pin "2") (pinfunction "C_2") (pintype "passive"))
      (node (ref "OK18") (pin "2") (pinfunction "C_2") (pintype "passive"))
      (node (ref "OK19") (pin "2") (pinfunction "C_2") (pintype "passive"))
      (node (ref "OK2") (pin "2") (pinfunction "C_2") (pintype "passive"))
      (node (ref "OK20") (pin "2") (pinfunction "C_2") (pintype "passive"))
      (node (ref "OK21") (pin "2") (pinfunction "C_2") (pintype "passive"))
      (node (ref "OK22") (pin "2") (pinfunction "C_2") (pintype "passive"))
      (node (ref "OK23") (pin "2") (pinfunction "C_2") (pintype "passive"))
      (node (ref "OK24") (pin "2") (pinfunction "C_2") (pintype "passive"))
      (node (ref "OK25") (pin "2") (pinfunction "C_2") (pintype "passive"))
      (node (ref "OK26") (pin "2") (pinfunction "C_2") (pintype "passive"))
      (node (ref "OK3") (pin "2") (pinfunction "C_2") (pintype "passive"))
      (node (ref "OK4") (pin "2") (pinfunction "C_2") (pintype "passive"))
      (node (ref "OK5") (pin "2") (pinfunction "C_2") (pintype "passive"))
      (node (ref "OK6") (pin "2") (pinfunction "C_2") (pintype "passive"))
      (node (ref "OK7") (pin "2") (pinfunction "C_2") (pintype "passive"))
      (node (ref "OK8") (pin "2") (pinfunction "C_2") (pintype "passive"))
      (node (ref "OK9") (pin "2") (pinfunction "C_2") (pintype "passive"))
      (node (ref "POWER_GND") (pin "1") (pinfunction "KL_1") (pintype "passive"))
      (node (ref "POWER_GND") (pin "2") (pinfunction "KL_2") (pintype "passive"))
      (node (ref "POWER_GND") (pin "3") (pinfunction "KL_3") (pintype "passive"))
      (node (ref "POWER_GND") (pin "4") (pinfunction "KL_4") (pintype "passive"))
      (node (ref "U$1") (pin "P$2") (pinfunction "P$2_P$2") (pintype "bidirectional"))
      (node (ref "U$10") (pin "P$2") (pinfunction "P$2_P$2") (pintype "bidirectional"))
      (node (ref "U$11") (pin "P$2") (pinfunction "P$2_P$2") (pintype "bidirectional"))
      (node (ref "U$12") (pin "P$2") (pinfunction "P$2_P$2") (pintype "bidirectional"))
      (node (ref "U$13") (pin "P$2") (pinfunction "P$2_P$2") (pintype "bidirectional"))
      (node (ref "U$14") (pin "P$2") (pinfunction "P$2_P$2") (pintype "bidirectional"))
      (node (ref "U$15") (pin "P$2") (pinfunction "P$2_P$2") (pintype "bidirectional"))
      (node (ref "U$16") (pin "P$2") (pinfunction "P$2_P$2") (pintype "bidirectional"))
      (node (ref "U$17") (pin "P$2") (pinfunction "P$2_P$2") (pintype "bidirectional"))
      (node (ref "U$18") (pin "P$2") (pinfunction "P$2_P$2") (pintype "bidirectional"))
      (node (ref "U$19") (pin "P$2") (pinfunction "P$2_P$2") (pintype "bidirectional"))
      (node (ref "U$2") (pin "P$2") (pinfunction "P$2_P$2") (pintype "bidirectional"))
      (node (ref "U$20") (pin "P$2") (pinfunction "P$2_P$2") (pintype "bidirectional"))
      (node (ref "U$21") (pin "P$2") (pinfunction "P$2_P$2") (pintype "bidirectional"))
      (node (ref "U$22") (pin "P$2") (pinfunction "P$2_P$2") (pintype "bidirectional"))
      (node (ref "U$23") (pin "P$2") (pinfunction "P$2_P$2") (pintype "bidirectional"))
      (node (ref "U$24") (pin "P$2") (pinfunction "P$2_P$2") (pintype "bidirectional"))
      (node (ref "U$3") (pin "P$2") (pinfunction "P$2_P$2") (pintype "bidirectional"))
      (node (ref "U$4") (pin "P$2") (pinfunction "P$2_P$2") (pintype "bidirectional"))
      (node (ref "U$5") (pin "P$2") (pinfunction "P$2_P$2") (pintype "bidirectional"))
      (node (ref "U$6") (pin "P$2") (pinfunction "P$2_P$2") (pintype "bidirectional"))
      (node (ref "U$7") (pin "P$2") (pinfunction "P$2_P$2") (pintype "bidirectional"))
      (node (ref "U$8") (pin "P$2") (pinfunction "P$2_P$2") (pintype "bidirectional"))
      (node (ref "U$9") (pin "P$2") (pinfunction "P$2_P$2") (pintype "bidirectional"))
      (node (ref "U1") (pin "CN11_19") (pinfunction "GND_CN11_CN11_19") (pintype "passive"))
      (node (ref "U1") (pin "CN11_20") (pinfunction "GND_CN11_CN11_20") (pintype "passive"))
      (node (ref "U1") (pin "CN11_22") (pinfunction "GND_CN11_CN11_22") (pintype "passive"))
      (node (ref "U1") (pin "CN11_49") (pinfunction "GND_CN11_CN11_49") (pintype "passive"))
      (node (ref "U1") (pin "CN11_60") (pinfunction "GND_CN11_CN11_60") (pintype "passive"))
      (node (ref "U1") (pin "CN11_71") (pinfunction "GND_CN11_CN11_71") (pintype "passive"))
      (node (ref "U1") (pin "CN11_72") (pinfunction "GND_CN11_CN11_72") (pintype "passive"))
      (node (ref "U1") (pin "CN11_8") (pinfunction "GND_CN11_CN11_8") (pintype "passive"))
      (node (ref "U1") (pin "CN12_20") (pinfunction "GND_CN12_CN12_20") (pintype "passive"))
      (node (ref "U1") (pin "CN12_39") (pinfunction "GND_CN12_CN12_39") (pintype "passive"))
      (node (ref "U1") (pin "CN12_54") (pinfunction "GND_CN12_CN12_54") (pintype "passive"))
      (node (ref "U1") (pin "CN12_63") (pinfunction "GND_CN12_CN12_63") (pintype "passive"))
      (node (ref "U1") (pin "CN12_71") (pinfunction "GND_CN12_CN12_71") (pintype "passive"))
      (node (ref "U1") (pin "CN12_72") (pinfunction "GND_CN12_CN12_72") (pintype "passive"))
      (node (ref "U1") (pin "CN12_9") (pinfunction "GND_CN12_CN12_9") (pintype "passive"))
    )
    (net (code "60") (name "GND1") (class "Default")
      (node (ref "EXT_GND") (pin "1") (pinfunction "KL_1") (pintype "passive"))
      (node (ref "EXT_GND") (pin "2") (pinfunction "KL_2") (pintype "passive"))
      (node (ref "Q1") (pin "E") (pinfunction "E_E") (pintype "passive"))
      (node (ref "Q10") (pin "E") (pinfunction "E_E") (pintype "passive"))
      (node (ref "Q11") (pin "E") (pinfunction "E_E") (pintype "passive"))
      (node (ref "Q12") (pin "E") (pinfunction "E_E") (pintype "passive"))
      (node (ref "Q13") (pin "E") (pinfunction "E_E") (pintype "passive"))
      (node (ref "Q14") (pin "E") (pinfunction "E_E") (pintype "passive"))
      (node (ref "Q15") (pin "E") (pinfunction "E_E") (pintype "passive"))
      (node (ref "Q16") (pin "E") (pinfunction "E_E") (pintype "passive"))
      (node (ref "Q17") (pin "E") (pinfunction "E_E") (pintype "passive"))
      (node (ref "Q18") (pin "E") (pinfunction "E_E") (pintype "passive"))
      (node (ref "Q19") (pin "E") (pinfunction "E_E") (pintype "passive"))
      (node (ref "Q2") (pin "E") (pinfunction "E_E") (pintype "passive"))
      (node (ref "Q20") (pin "E") (pinfunction "E_E") (pintype "passive"))
      (node (ref "Q21") (pin "E") (pinfunction "E_E") (pintype "passive"))
      (node (ref "Q22") (pin "E") (pinfunction "E_E") (pintype "passive"))
      (node (ref "Q23") (pin "E") (pinfunction "E_E") (pintype "passive"))
      (node (ref "Q24") (pin "E") (pinfunction "E_E") (pintype "passive"))
      (node (ref "Q25") (pin "E") (pinfunction "E_E") (pintype "passive"))
      (node (ref "Q26") (pin "E") (pinfunction "E_E") (pintype "passive"))
      (node (ref "Q3") (pin "E") (pinfunction "E_E") (pintype "passive"))
      (node (ref "Q4") (pin "E") (pinfunction "E_E") (pintype "passive"))
      (node (ref "Q5") (pin "E") (pinfunction "E_E") (pintype "passive"))
      (node (ref "Q6") (pin "E") (pinfunction "E_E") (pintype "passive"))
      (node (ref "Q7") (pin "E") (pinfunction "E_E") (pintype "passive"))
      (node (ref "Q8") (pin "E") (pinfunction "E_E") (pintype "passive"))
      (node (ref "Q9") (pin "E") (pinfunction "E_E") (pintype "passive"))
    )
    (net (code "61") (name "Net-(LIGHTSA-KL)") (class "Default")
      (node (ref "LIGHTS") (pin "1") (pinfunction "KL_1") (pintype "passive"))
      (node (ref "LIGHTS") (pin "2") (pinfunction "KL_2") (pintype "passive"))
      (node (ref "OK25") (pin "4") (pinfunction "COL_4") (pintype "passive"))
      (node (ref "Q26") (pin "C") (pinfunction "C_C") (pintype "passive"))
    )
    (net (code "62") (name "Net-(OK1-A)") (class "Default")
      (node (ref "OK1") (pin "1") (pinfunction "A_1") (pintype "passive"))
      (node (ref "R1") (pin "2") (pinfunction "2_2") (pintype "passive"))
    )
    (net (code "63") (name "Net-(OK1-EMIT)") (class "Default")
      (node (ref "OK1") (pin "3") (pinfunction "EMIT_3") (pintype "passive"))
      (node (ref "Q1") (pin "B") (pinfunction "B_B") (pintype "passive"))
    )
    (net (code "64") (name "Net-(OK2-A)") (class "Default")
      (node (ref "OK2") (pin "1") (pinfunction "A_1") (pintype "passive"))
      (node (ref "R2") (pin "2") (pinfunction "2_2") (pintype "passive"))
    )
    (net (code "65") (name "Net-(OK2-EMIT)") (class "Default")
      (node (ref "OK2") (pin "3") (pinfunction "EMIT_3") (pintype "passive"))
      (node (ref "Q2") (pin "B") (pinfunction "B_B") (pintype "passive"))
    )
    (net (code "66") (name "Net-(OK3-A)") (class "Default")
      (node (ref "OK3") (pin "1") (pinfunction "A_1") (pintype "passive"))
      (node (ref "R3") (pin "2") (pinfunction "2_2") (pintype "passive"))
    )
    (net (code "67") (name "Net-(OK3-EMIT)") (class "Default")
      (node (ref "OK3") (pin "3") (pinfunction "EMIT_3") (pintype "passive"))
      (node (ref "Q3") (pin "B") (pinfunction "B_B") (pintype "passive"))
    )
    (net (code "68") (name "Net-(OK4-A)") (class "Default")
      (node (ref "OK4") (pin "1") (pinfunction "A_1") (pintype "passive"))
      (node (ref "R4") (pin "2") (pinfunction "2_2") (pintype "passive"))
    )
    (net (code "69") (name "Net-(OK4-EMIT)") (class "Default")
      (node (ref "OK4") (pin "3") (pinfunction "EMIT_3") (pintype "passive"))
      (node (ref "Q4") (pin "B") (pinfunction "B_B") (pintype "passive"))
    )
    (net (code "70") (name "Net-(OK5-A)") (class "Default")
      (node (ref "OK5") (pin "1") (pinfunction "A_1") (pintype "passive"))
      (node (ref "R5") (pin "2") (pinfunction "2_2") (pintype "passive"))
    )
    (net (code "71") (name "Net-(OK5-EMIT)") (class "Default")
      (node (ref "OK5") (pin "3") (pinfunction "EMIT_3") (pintype "passive"))
      (node (ref "Q5") (pin "B") (pinfunction "B_B") (pintype "passive"))
    )
    (net (code "72") (name "Net-(OK6-A)") (class "Default")
      (node (ref "OK6") (pin "1") (pinfunction "A_1") (pintype "passive"))
      (node (ref "R6") (pin "2") (pinfunction "2_2") (pintype "passive"))
    )
    (net (code "73") (name "Net-(OK6-EMIT)") (class "Default")
      (node (ref "OK6") (pin "3") (pinfunction "EMIT_3") (pintype "passive"))
      (node (ref "Q6") (pin "B") (pinfunction "B_B") (pintype "passive"))
    )
    (net (code "74") (name "Net-(OK7-A)") (class "Default")
      (node (ref "OK7") (pin "1") (pinfunction "A_1") (pintype "passive"))
      (node (ref "R7") (pin "2") (pinfunction "2_2") (pintype "passive"))
    )
    (net (code "75") (name "Net-(OK7-EMIT)") (class "Default")
      (node (ref "OK7") (pin "3") (pinfunction "EMIT_3") (pintype "passive"))
      (node (ref "Q7") (pin "B") (pinfunction "B_B") (pintype "passive"))
    )
    (net (code "76") (name "Net-(OK8-A)") (class "Default")
      (node (ref "OK8") (pin "1") (pinfunction "A_1") (pintype "passive"))
      (node (ref "R8") (pin "2") (pinfunction "2_2") (pintype "passive"))
    )
    (net (code "77") (name "Net-(OK8-EMIT)") (class "Default")
      (node (ref "OK8") (pin "3") (pinfunction "EMIT_3") (pintype "passive"))
      (node (ref "Q8") (pin "B") (pinfunction "B_B") (pintype "passive"))
    )
    (net (code "78") (name "Net-(OK9-A)") (class "Default")
      (node (ref "OK9") (pin "1") (pinfunction "A_1") (pintype "passive"))
      (node (ref "R9") (pin "2") (pinfunction "2_2") (pintype "passive"))
    )
    (net (code "79") (name "Net-(OK9-COL)") (class "Default")
      (node (ref "OK9") (pin "4") (pinfunction "COL_4") (pintype "passive"))
      (node (ref "Q16") (pin "C") (pinfunction "C_C") (pintype "passive"))
      (node (ref "X1") (pin "8") (pinfunction "KL_8") (pintype "passive"))
    )
    (net (code "80") (name "Net-(OK9-EMIT)") (class "Default")
      (node (ref "OK9") (pin "3") (pinfunction "EMIT_3") (pintype "passive"))
      (node (ref "Q16") (pin "B") (pinfunction "B_B") (pintype "passive"))
    )
    (net (code "81") (name "Net-(OK10-A)") (class "Default")
      (node (ref "OK10") (pin "1") (pinfunction "A_1") (pintype "passive"))
      (node (ref "R10") (pin "2") (pinfunction "2_2") (pintype "passive"))
    )
    (net (code "82") (name "Net-(OK10-COL)") (class "Default")
      (node (ref "OK10") (pin "4") (pinfunction "COL_4") (pintype "passive"))
      (node (ref "Q15") (pin "C") (pinfunction "C_C") (pintype "passive"))
      (node (ref "X1") (pin "7") (pinfunction "KL_7") (pintype "passive"))
    )
    (net (code "83") (name "Net-(OK10-EMIT)") (class "Default")
      (node (ref "OK10") (pin "3") (pinfunction "EMIT_3") (pintype "passive"))
      (node (ref "Q15") (pin "B") (pinfunction "B_B") (pintype "passive"))
    )
    (net (code "84") (name "Net-(OK11-A)") (class "Default")
      (node (ref "OK11") (pin "1") (pinfunction "A_1") (pintype "passive"))
      (node (ref "R11") (pin "2") (pinfunction "2_2") (pintype "passive"))
    )
    (net (code "85") (name "Net-(OK11-COL)") (class "Default")
      (node (ref "OK11") (pin "4") (pinfunction "COL_4") (pintype "passive"))
      (node (ref "Q14") (pin "C") (pinfunction "C_C") (pintype "passive"))
      (node (ref "X1") (pin "6") (pinfunction "KL_6") (pintype "passive"))
    )
    (net (code "86") (name "Net-(OK11-EMIT)") (class "Default")
      (node (ref "OK11") (pin "3") (pinfunction "EMIT_3") (pintype "passive"))
      (node (ref "Q14") (pin "B") (pinfunction "B_B") (pintype "passive"))
    )
    (net (code "87") (name "Net-(OK12-A)") (class "Default")
      (node (ref "OK12") (pin "1") (pinfunction "A_1") (pintype "passive"))
      (node (ref "R12") (pin "2") (pinfunction "2_2") (pintype "passive"))
    )
    (net (code "88") (name "Net-(OK12-COL)") (class "Default")
      (node (ref "OK12") (pin "4") (pinfunction "COL_4") (pintype "passive"))
      (node (ref "Q13") (pin "C") (pinfunction "C_C") (pintype "passive"))
      (node (ref "X1") (pin "5") (pinfunction "KL_5") (pintype "passive"))
    )
    (net (code "89") (name "Net-(OK12-EMIT)") (class "Default")
      (node (ref "OK12") (pin "3") (pinfunction "EMIT_3") (pintype "passive"))
      (node (ref "Q13") (pin "B") (pinfunction "B_B") (pintype "passive"))
    )
    (net (code "90") (name "Net-(OK13-A)") (class "Default")
      (node (ref "OK13") (pin "1") (pinfunction "A_1") (pintype "passive"))
      (node (ref "R13") (pin "2") (pinfunction "2_2") (pintype "passive"))
    )
    (net (code "91") (name "Net-(OK13-COL)") (class "Default")
      (node (ref "OK13") (pin "4") (pinfunction "COL_4") (pintype "passive"))
      (node (ref "Q12") (pin "C") (pinfunction "C_C") (pintype "passive"))
      (node (ref "X1") (pin "4") (pinfunction "KL_4") (pintype "passive"))
    )
    (net (code "92") (name "Net-(OK13-EMIT)") (class "Default")
      (node (ref "OK13") (pin "3") (pinfunction "EMIT_3") (pintype "passive"))
      (node (ref "Q12") (pin "B") (pinfunction "B_B") (pintype "passive"))
    )
    (net (code "93") (name "Net-(OK14-A)") (class "Default")
      (node (ref "OK14") (pin "1") (pinfunction "A_1") (pintype "passive"))
      (node (ref "R14") (pin "2") (pinfunction "2_2") (pintype "passive"))
    )
    (net (code "94") (name "Net-(OK14-COL)") (class "Default")
      (node (ref "OK14") (pin "4") (pinfunction "COL_4") (pintype "passive"))
      (node (ref "Q11") (pin "C") (pinfunction "C_C") (pintype "passive"))
      (node (ref "X1") (pin "3") (pinfunction "KL_3") (pintype "passive"))
    )
    (net (code "95") (name "Net-(OK14-EMIT)") (class "Default")
      (node (ref "OK14") (pin "3") (pinfunction "EMIT_3") (pintype "passive"))
      (node (ref "Q11") (pin "B") (pinfunction "B_B") (pintype "passive"))
    )
    (net (code "96") (name "Net-(OK15-A)") (class "Default")
      (node (ref "OK15") (pin "1") (pinfunction "A_1") (pintype "passive"))
      (node (ref "R15") (pin "2") (pinfunction "2_2") (pintype "passive"))
    )
    (net (code "97") (name "Net-(OK15-COL)") (class "Default")
      (node (ref "OK15") (pin "4") (pinfunction "COL_4") (pintype "passive"))
      (node (ref "Q10") (pin "C") (pinfunction "C_C") (pintype "passive"))
      (node (ref "X1") (pin "2") (pinfunction "KL_2") (pintype "passive"))
    )
    (net (code "98") (name "Net-(OK15-EMIT)") (class "Default")
      (node (ref "OK15") (pin "3") (pinfunction "EMIT_3") (pintype "passive"))
      (node (ref "Q10") (pin "B") (pinfunction "B_B") (pintype "passive"))
    )
    (net (code "99") (name "Net-(OK16-A)") (class "Default")
      (node (ref "OK16") (pin "1") (pinfunction "A_1") (pintype "passive"))
      (node (ref "R16") (pin "2") (pinfunction "2_2") (pintype "passive"))
    )
    (net (code "100") (name "Net-(OK16-COL)") (class "Default")
      (node (ref "OK16") (pin "4") (pinfunction "COL_4") (pintype "passive"))
      (node (ref "Q9") (pin "C") (pinfunction "C_C") (pintype "passive"))
      (node (ref "X1") (pin "1") (pinfunction "KL_1") (pintype "passive"))
    )
    (net (code "101") (name "Net-(OK16-EMIT)") (class "Default")
      (node (ref "OK16") (pin "3") (pinfunction "EMIT_3") (pintype "passive"))
      (node (ref "Q9") (pin "B") (pinfunction "B_B") (pintype "passive"))
    )
    (net (code "102") (name "Net-(OK17-A)") (class "Default")
      (node (ref "OK17") (pin "1") (pinfunction "A_1") (pintype "passive"))
      (node (ref "R17") (pin "2") (pinfunction "2_2") (pintype "passive"))
    )
    (net (code "103") (name "Net-(OK17-COL)") (class "Default")
      (node (ref "OK17") (pin "4") (pinfunction "COL_4") (pintype "passive"))
      (node (ref "Q17") (pin "C") (pinfunction "C_C") (pintype "passive"))
      (node (ref "X2") (pin "8") (pinfunction "KL_8") (pintype "passive"))
    )
    (net (code "104") (name "Net-(OK17-EMIT)") (class "Default")
      (node (ref "OK17") (pin "3") (pinfunction "EMIT_3") (pintype "passive"))
      (node (ref "Q17") (pin "B") (pinfunction "B_B") (pintype "passive"))
    )
    (net (code "105") (name "Net-(OK18-A)") (class "Default")
      (node (ref "OK18") (pin "1") (pinfunction "A_1") (pintype "passive"))
      (node (ref "R18") (pin "2") (pinfunction "2_2") (pintype "passive"))
    )
    (net (code "106") (name "Net-(OK18-COL)") (class "Default")
      (node (ref "OK18") (pin "4") (pinfunction "COL_4") (pintype "passive"))
      (node (ref "Q18") (pin "C") (pinfunction "C_C") (pintype "passive"))
      (node (ref "X2") (pin "7") (pinfunction "KL_7") (pintype "passive"))
    )
    (net (code "107") (name "Net-(OK18-EMIT)") (class "Default")
      (node (ref "OK18") (pin "3") (pinfunction "EMIT_3") (pintype "passive"))
      (node (ref "Q18") (pin "B") (pinfunction "B_B") (pintype "passive"))
    )
    (net (code "108") (name "Net-(OK19-A)") (class "Default")
      (node (ref "OK19") (pin "1") (pinfunction "A_1") (pintype "passive"))
      (node (ref "R19") (pin "2") (pinfunction "2_2") (pintype "passive"))
    )
    (net (code "109") (name "Net-(OK19-COL)") (class "Default")
      (node (ref "OK19") (pin "4") (pinfunction "COL_4") (pintype "passive"))
      (node (ref "Q19") (pin "C") (pinfunction "C_C") (pintype "passive"))
      (node (ref "X2") (pin "6") (pinfunction "KL_6") (pintype "passive"))
    )
    (net (code "110") (name "Net-(OK19-EMIT)") (class "Default")
      (node (ref "OK19") (pin "3") (pinfunction "EMIT_3") (pintype "passive"))
      (node (ref "Q19") (pin "B") (pinfunction "B_B") (pintype "passive"))
    )
    (net (code "111") (name "Net-(OK20-A)") (class "Default")
      (node (ref "OK20") (pin "1") (pinfunction "A_1") (pintype "passive"))
      (node (ref "R20") (pin "2") (pinfunction "2_2") (pintype "passive"))
    )
    (net (code "112") (name "Net-(OK20-COL)") (class "Default")
      (node (ref "OK20") (pin "4") (pinfunction "COL_4") (pintype "passive"))
      (node (ref "Q20") (pin "C") (pinfunction "C_C") (pintype "passive"))
      (node (ref "X2") (pin "5") (pinfunction "KL_5") (pintype "passive"))
    )
    (net (code "113") (name "Net-(OK20-EMIT)") (class "Default")
      (node (ref "OK20") (pin "3") (pinfunction "EMIT_3") (pintype "passive"))
      (node (ref "Q20") (pin "B") (pinfunction "B_B") (pintype "passive"))
    )
    (net (code "114") (name "Net-(OK21-A)") (class "Default")
      (node (ref "OK21") (pin "1") (pinfunction "A_1") (pintype "passive"))
      (node (ref "R21") (pin "2") (pinfunction "2_2") (pintype "passive"))
    )
    (net (code "115") (name "Net-(OK21-COL)") (class "Default")
      (node (ref "OK21") (pin "4") (pinfunction "COL_4") (pintype "passive"))
      (node (ref "Q21") (pin "C") (pinfunction "C_C") (pintype "passive"))
      (node (ref "X2") (pin "4") (pinfunction "KL_4") (pintype "passive"))
    )
    (net (code "116") (name "Net-(OK21-EMIT)") (class "Default")
      (node (ref "OK21") (pin "3") (pinfunction "EMIT_3") (pintype "passive"))
      (node (ref "Q21") (pin "B") (pinfunction "B_B") (pintype "passive"))
    )
    (net (code "117") (name "Net-(OK22-A)") (class "Default")
      (node (ref "OK22") (pin "1") (pinfunction "A_1") (pintype "passive"))
      (node (ref "R22") (pin "2") (pinfunction "2_2") (pintype "passive"))
    )
    (net (code "118") (name "Net-(OK22-COL)") (class "Default")
      (node (ref "OK22") (pin "4") (pinfunction "COL_4") (pintype "passive"))
      (node (ref "Q22") (pin "C") (pinfunction "C_C") (pintype "passive"))
      (node (ref "X2") (pin "3") (pinfunction "KL_3") (pintype "passive"))
    )
    (net (code "119") (name "Net-(OK22-EMIT)") (class "Default")
      (node (ref "OK22") (pin "3") (pinfunction "EMIT_3") (pintype "passive"))
      (node (ref "Q22") (pin "B") (pinfunction "B_B") (pintype "passive"))
    )
    (net (code "120") (name "Net-(OK23-A)") (class "Default")
      (node (ref "OK23") (pin "1") (pinfunction "A_1") (pintype "passive"))
      (node (ref "R23") (pin "2") (pinfunction "2_2") (pintype "passive"))
    )
    (net (code "121") (name "Net-(OK23-COL)") (class "Default")
      (node (ref "OK23") (pin "4") (pinfunction "COL_4") (pintype "passive"))
      (node (ref "Q23") (pin "C") (pinfunction "C_C") (pintype "passive"))
      (node (ref "X2") (pin "2") (pinfunction "KL_2") (pintype "passive"))
    )
    (net (code "122") (name "Net-(OK23-EMIT)") (class "Default")
      (node (ref "OK23") (pin "3") (pinfunction "EMIT_3") (pintype "passive"))
      (node (ref "Q23") (pin "B") (pinfunction "B_B") (pintype "passive"))
    )
    (net (code "123") (name "Net-(OK24-A)") (class "Default")
      (node (ref "OK24") (pin "1") (pinfunction "A_1") (pintype "passive"))
      (node (ref "R24") (pin "2") (pinfunction "2_2") (pintype "passive"))
    )
    (net (code "124") (name "Net-(OK24-COL)") (class "Default")
      (node (ref "OK24") (pin "4") (pinfunction "COL_4") (pintype "passive"))
      (node (ref "Q24") (pin "C") (pinfunction "C_C") (pintype "passive"))
      (node (ref "X2") (pin "1") (pinfunction "KL_1") (pintype "passive"))
    )
    (net (code "125") (name "Net-(OK24-EMIT)") (class "Default")
      (node (ref "OK24") (pin "3") (pinfunction "EMIT_3") (pintype "passive"))
      (node (ref "Q24") (pin "B") (pinfunction "B_B") (pintype "passive"))
    )
    (net (code "126") (name "Net-(OK25-A)") (class "Default")
      (node (ref "OK25") (pin "1") (pinfunction "A_1") (pintype "passive"))
      (node (ref "R49") (pin "2") (pinfunction "2_2") (pintype "passive"))
    )
    (net (code "127") (name "Net-(OK25-EMIT)") (class "Default")
      (node (ref "OK25") (pin "3") (pinfunction "EMIT_3") (pintype "passive"))
      (node (ref "Q26") (pin "B") (pinfunction "B_B") (pintype "passive"))
    )
    (net (code "128") (name "Net-(OK26-A)") (class "Default")
      (node (ref "OK26") (pin "1") (pinfunction "A_1") (pintype "passive"))
      (node (ref "R50") (pin "2") (pinfunction "2_2") (pintype "passive"))
    )
    (net (code "129") (name "Net-(OK26-COL)") (class "Default")
      (node (ref "OK26") (pin "4") (pinfunction "COL_4") (pintype "passive"))
      (node (ref "Q25") (pin "C") (pinfunction "C_C") (pintype "passive"))
      (node (ref "RELE_EN") (pin "1") (pinfunction "KL_1") (pintype "passive"))
      (node (ref "RELE_EN") (pin "2") (pinfunction "KL_2") (pintype "passive"))
    )
    (net (code "130") (name "Net-(OK26-EMIT)") (class "Default")
      (node (ref "OK26") (pin "3") (pinfunction "EMIT_3") (pintype "passive"))
      (node (ref "Q25") (pin "B") (pinfunction "B_B") (pintype "passive"))
    )
    (net (code "131") (name "VCC") (class "Default")
      (node (ref "POWER_5V") (pin "1") (pinfunction "KL_1") (pintype "passive"))
      (node (ref "POWER_5V") (pin "2") (pinfunction "KL_2") (pintype "passive"))
      (node (ref "POWER_5V") (pin "3") (pinfunction "KL_3") (pintype "passive"))
      (node (ref "POWER_5V") (pin "4") (pinfunction "KL_4") (pintype "passive"))
      (node (ref "R25") (pin "2") (pinfunction "2_2") (pintype "passive"))
      (node (ref "R26") (pin "2") (pinfunction "2_2") (pintype "passive"))
      (node (ref "R27") (pin "2") (pinfunction "2_2") (pintype "passive"))
      (node (ref "R28") (pin "2") (pinfunction "2_2") (pintype "passive"))
      (node (ref "R29") (pin "2") (pinfunction "2_2") (pintype "passive"))
      (node (ref "R30") (pin "2") (pinfunction "2_2") (pintype "passive"))
      (node (ref "R31") (pin "2") (pinfunction "2_2") (pintype "passive"))
      (node (ref "R32") (pin "2") (pinfunction "2_2") (pintype "passive"))
      (node (ref "R33") (pin "2") (pinfunction "2_2") (pintype "passive"))
      (node (ref "R34") (pin "2") (pinfunction "2_2") (pintype "passive"))
      (node (ref "R35") (pin "2") (pinfunction "2_2") (pintype "passive"))
      (node (ref "R36") (pin "2") (pinfunction "2_2") (pintype "passive"))
      (node (ref "R37") (pin "2") (pinfunction "2_2") (pintype "passive"))
      (node (ref "R38") (pin "2") (pinfunction "2_2") (pintype "passive"))
      (node (ref "R39") (pin "2") (pinfunction "2_2") (pintype "passive"))
      (node (ref "R40") (pin "2") (pinfunction "2_2") (pintype "passive"))
      (node (ref "R41") (pin "2") (pinfunction "2_2") (pintype "passive"))
      (node (ref "R42") (pin "2") (pinfunction "2_2") (pintype "passive"))
      (node (ref "R43") (pin "2") (pinfunction "2_2") (pintype "passive"))
      (node (ref "R44") (pin "2") (pinfunction "2_2") (pintype "passive"))
      (node (ref "R45") (pin "2") (pinfunction "2_2") (pintype "passive"))
      (node (ref "R46") (pin "2") (pinfunction "2_2") (pintype "passive"))
      (node (ref "R47") (pin "2") (pinfunction "2_2") (pintype "passive"))
      (node (ref "R48") (pin "2") (pinfunction "2_2") (pintype "passive"))
      (node (ref "U1") (pin "CN11_18") (pinfunction "+5V_CN11_18") (pintype "passive"))
    )
    (net (code "132") (name "unconnected-(U1E-+3.3V-PadCN11_16)") (class "Default")
      (node (ref "U1") (pin "CN11_16") (pinfunction "+3.3V_CN11_16") (pintype "passive"))
    )
    (net (code "133") (name "unconnected-(U1E-BOOT0-PadCN11_7)") (class "Default")
      (node (ref "U1") (pin "CN11_7") (pinfunction "BOOT0_CN11_7") (pintype "passive"))
    )
    (net (code "134") (name "unconnected-(U1E-E5V-PadCN11_6)") (class "Default")
      (node (ref "U1") (pin "CN11_6") (pinfunction "E5V_CN11_6") (pintype "passive"))
    )
    (net (code "135") (name "unconnected-(U1E-IOREF-PadCN11_12)") (class "Default")
      (node (ref "U1") (pin "CN11_12") (pinfunction "IOREF_CN11_12") (pintype "passive"))
    )
    (net (code "136") (name "unconnected-(U1E-PA0-PadCN11_28)") (class "Default")
      (node (ref "U1") (pin "CN11_28") (pinfunction "PA0_CN11_28") (pintype "passive"))
    )
    (net (code "137") (name "unconnected-(U1E-PA1-PadCN11_30)") (class "Default")
      (node (ref "U1") (pin "CN11_30") (pinfunction "PA1_CN11_30") (pintype "passive"))
    )
    (net (code "138") (name "unconnected-(U1E-PB0-PadCN11_34)") (class "Default")
      (node (ref "U1") (pin "CN11_34") (pinfunction "PB0_CN11_34") (pintype "passive"))
    )
    (net (code "139") (name "unconnected-(U1E-PB7-PadCN11_21)") (class "Default")
      (node (ref "U1") (pin "CN11_21") (pinfunction "PB7_CN11_21") (pintype "passive"))
    )
    (net (code "140") (name "unconnected-(U1E-PC0-PadCN11_38)") (class "Default")
      (node (ref "U1") (pin "CN11_38") (pinfunction "PC0_CN11_38") (pintype "passive"))
    )
    (net (code "141") (name "unconnected-(U1E-PC1-PadCN11_36)") (class "Default")
      (node (ref "U1") (pin "CN11_36") (pinfunction "PC1_CN11_36") (pintype "passive"))
    )
    (net (code "142") (name "unconnected-(U1E-PC11-PadCN11_2)") (class "Default")
      (node (ref "U1") (pin "CN11_2") (pinfunction "PC11_CN11_2") (pintype "passive"))
    )
    (net (code "143") (name "unconnected-(U1E-PC14-PadCN11_25)") (class "Default")
      (node (ref "U1") (pin "CN11_25") (pinfunction "PC14_CN11_25") (pintype "passive"))
    )
    (net (code "144") (name "unconnected-(U1E-PC15-PadCN11_27)") (class "Default")
      (node (ref "U1") (pin "CN11_27") (pinfunction "PC15_CN11_27") (pintype "passive"))
    )
    (net (code "145") (name "unconnected-(U1E-PD2-PadCN11_4)") (class "Default")
      (node (ref "U1") (pin "CN11_4") (pinfunction "PD2_CN11_4") (pintype "passive"))
    )
    (net (code "146") (name "unconnected-(U1E-PD3-PadCN11_40)") (class "Default")
      (node (ref "U1") (pin "CN11_40") (pinfunction "PD3_CN11_40") (pintype "passive"))
    )
    (net (code "147") (name "unconnected-(U1E-PD9-PadCN11_69)") (class "Default")
      (node (ref "U1") (pin "CN11_69") (pinfunction "PD9_CN11_69") (pintype "passive"))
    )
    (net (code "148") (name "unconnected-(U1E-PE2-PadCN11_46)") (class "Default")
      (node (ref "U1") (pin "CN11_46") (pinfunction "PE2_CN11_46") (pintype "passive"))
    )
    (net (code "149") (name "unconnected-(U1E-PE4-PadCN11_48)") (class "Default")
      (node (ref "U1") (pin "CN11_48") (pinfunction "PE4_CN11_48") (pintype "passive"))
    )
    (net (code "150") (name "unconnected-(U1E-PE5-PadCN11_50)") (class "Default")
      (node (ref "U1") (pin "CN11_50") (pinfunction "PE5_CN11_50") (pintype "passive"))
    )
    (net (code "151") (name "unconnected-(U1E-PE6-PadCN11_62)") (class "Default")
      (node (ref "U1") (pin "CN11_62") (pinfunction "PE6_CN11_62") (pintype "passive"))
    )
    (net (code "152") (name "unconnected-(U1E-PF2-PadCN11_52)") (class "Default")
      (node (ref "U1") (pin "CN11_52") (pinfunction "PF2_CN11_52") (pintype "passive"))
    )
    (net (code "153") (name "unconnected-(U1E-PF8-PadCN11_54)") (class "Default")
      (node (ref "U1") (pin "CN11_54") (pinfunction "PF8_CN11_54") (pintype "passive"))
    )
    (net (code "154") (name "unconnected-(U1E-PF9-PadCN11_56)") (class "Default")
      (node (ref "U1") (pin "CN11_56") (pinfunction "PF9_CN11_56") (pintype "passive"))
    )
    (net (code "155") (name "unconnected-(U1E-PG1-PadCN11_58)") (class "Default")
      (node (ref "U1") (pin "CN11_58") (pinfunction "PG1_CN11_58") (pintype "passive"))
    )
    (net (code "156") (name "unconnected-(U1E-PG2-PadCN11_42)") (class "Default")
      (node (ref "U1") (pin "CN11_42") (pinfunction "PG2_CN11_42") (pintype "passive"))
    )
    (net (code "157") (name "unconnected-(U1E-PG3-PadCN11_44)") (class "Default")
      (node (ref "U1") (pin "CN11_44") (pinfunction "PG3_CN11_44") (pintype "passive"))
    )
    (net (code "158") (name "unconnected-(U1E-PG10-PadCN11_66)") (class "Default")
      (node (ref "U1") (pin "CN11_66") (pinfunction "PG10_CN11_66") (pintype "passive"))
    )
    (net (code "159") (name "unconnected-(U1E-PG11-PadCN11_70)") (class "Default")
      (node (ref "U1") (pin "CN11_70") (pinfunction "PG11_CN11_70") (pintype "passive"))
    )
    (net (code "160") (name "unconnected-(U1E-PG13-PadCN11_68)") (class "Default")
      (node (ref "U1") (pin "CN11_68") (pinfunction "PG13_CN11_68") (pintype "passive"))
    )
    (net (code "161") (name "unconnected-(U1E-PG15-PadCN11_64)") (class "Default")
      (node (ref "U1") (pin "CN11_64") (pinfunction "PG15_CN11_64") (pintype "passive"))
    )
    (net (code "162") (name "unconnected-(U1E-PH0-PadCN11_29)") (class "Default")
      (node (ref "U1") (pin "CN11_29") (pinfunction "PH0_CN11_29") (pintype "passive"))
    )
    (net (code "163") (name "unconnected-(U1E-PH1-PadCN11_31)") (class "Default")
      (node (ref "U1") (pin "CN11_31") (pinfunction "PH1_CN11_31") (pintype "passive"))
    )
    (net (code "164") (name "unconnected-(U1E-RESET-PadCN11_14)") (class "Default")
      (node (ref "U1") (pin "CN11_14") (pinfunction "RESET_CN11_14") (pintype "passive"))
    )
    (net (code "165") (name "unconnected-(U1E-VBAT-PadCN11_33)") (class "Default")
      (node (ref "U1") (pin "CN11_33") (pinfunction "VBAT_CN11_33") (pintype "passive"))
    )
    (net (code "166") (name "unconnected-(U1E-VDD-PadCN11_5)") (class "Default")
      (node (ref "U1") (pin "CN11_5") (pinfunction "VDD_CN11_5") (pintype "passive"))
    )
    (net (code "167") (name "unconnected-(U1E-VIN-PadCN11_24)") (class "Default")
      (node (ref "U1") (pin "CN11_24") (pinfunction "VIN_CN11_24") (pintype "passive"))
    )
    (net (code "168") (name "unconnected-(U1F-AGND-PadCN12_32)") (class "Default")
      (node (ref "U1") (pin "CN12_32") (pinfunction "AGND_CN12_32") (pintype "passive"))
    )
    (net (code "169") (name "unconnected-(U1F-AVDD-PadCN12_7)") (class "Default")
      (node (ref "U1") (pin "CN12_7") (pinfunction "AVDD_CN12_7") (pintype "passive"))
    )
    (net (code "170") (name "unconnected-(U1F-PA2-PadCN12_35)") (class "Default")
      (node (ref "U1") (pin "CN12_35") (pinfunction "PA2_CN12_35") (pintype "passive"))
    )
    (net (code "171") (name "unconnected-(U1F-PA3-PadCN12_37)") (class "Default")
      (node (ref "U1") (pin "CN12_37") (pinfunction "PA3_CN12_37") (pintype "passive"))
    )
    (net (code "172") (name "unconnected-(U1F-PA5-PadCN12_11)") (class "Default")
      (node (ref "U1") (pin "CN12_11") (pinfunction "PA5_CN12_11") (pintype "passive"))
    )
    (net (code "173") (name "unconnected-(U1F-PA6-PadCN12_13)") (class "Default")
      (node (ref "U1") (pin "CN12_13") (pinfunction "PA6_CN12_13") (pintype "passive"))
    )
    (net (code "174") (name "unconnected-(U1F-PA7-PadCN12_15)") (class "Default")
      (node (ref "U1") (pin "CN12_15") (pinfunction "PA7_CN12_15") (pintype "passive"))
    )
    (net (code "175") (name "unconnected-(U1F-PA8-PadCN12_23)") (class "Default")
      (node (ref "U1") (pin "CN12_23") (pinfunction "PA8_CN12_23") (pintype "passive"))
    )
    (net (code "176") (name "unconnected-(U1F-PA9-PadCN12_21)") (class "Default")
      (node (ref "U1") (pin "CN12_21") (pinfunction "PA9_CN12_21") (pintype "passive"))
    )
    (net (code "177") (name "unconnected-(U1F-PA10-PadCN12_33)") (class "Default")
      (node (ref "U1") (pin "CN12_33") (pinfunction "PA10_CN12_33") (pintype "passive"))
    )
    (net (code "178") (name "unconnected-(U1F-PA11-PadCN12_14)") (class "Default")
      (node (ref "U1") (pin "CN12_14") (pinfunction "PA11_CN12_14") (pintype "passive"))
    )
    (net (code "179") (name "unconnected-(U1F-PA12-PadCN12_12)") (class "Default")
      (node (ref "U1") (pin "CN12_12") (pinfunction "PA12_CN12_12") (pintype "passive"))
    )
    (net (code "180") (name "unconnected-(U1F-PB3-PadCN12_31)") (class "Default")
      (node (ref "U1") (pin "CN12_31") (pinfunction "PB3_CN12_31") (pintype "passive"))
    )
    (net (code "181") (name "unconnected-(U1F-PB4-PadCN12_27)") (class "Default")
      (node (ref "U1") (pin "CN12_27") (pinfunction "PB4_CN12_27") (pintype "passive"))
    )
    (net (code "182") (name "unconnected-(U1F-PB5-PadCN12_29)") (class "Default")
      (node (ref "U1") (pin "CN12_29") (pinfunction "PB5_CN12_29") (pintype "passive"))
    )
    (net (code "183") (name "unconnected-(U1F-PB6-PadCN12_17)") (class "Default")
      (node (ref "U1") (pin "CN12_17") (pinfunction "PB6_CN12_17") (pintype "passive"))
    )
    (net (code "184") (name "unconnected-(U1F-PB9-PadCN12_5)") (class "Default")
      (node (ref "U1") (pin "CN12_5") (pinfunction "PB9_CN12_5") (pintype "passive"))
    )
    (net (code "185") (name "unconnected-(U1F-PB10-PadCN12_25)") (class "Default")
      (node (ref "U1") (pin "CN12_25") (pinfunction "PB10_CN12_25") (pintype "passive"))
    )
    (net (code "186") (name "unconnected-(U1F-PB13-PadCN12_30)") (class "Default")
      (node (ref "U1") (pin "CN12_30") (pinfunction "PB13_CN12_30") (pintype "passive"))
    )
    (net (code "187") (name "unconnected-(U1F-PB14-PadCN12_28)") (class "Default")
      (node (ref "U1") (pin "CN12_28") (pinfunction "PB14_CN12_28") (pintype "passive"))
    )
    (net (code "188") (name "unconnected-(U1F-PC4-PadCN12_34)") (class "Default")
      (node (ref "U1") (pin "CN12_34") (pinfunction "PC4_CN12_34") (pintype "passive"))
    )
    (net (code "189") (name "unconnected-(U1F-PC5-PadCN12_6)") (class "Default")
      (node (ref "U1") (pin "CN12_6") (pinfunction "PC5_CN12_6") (pintype "passive"))
    )
    (net (code "190") (name "unconnected-(U1F-PC7-PadCN12_19)") (class "Default")
      (node (ref "U1") (pin "CN12_19") (pinfunction "PC7_CN12_19") (pintype "passive"))
    )
    (net (code "191") (name "unconnected-(U1F-PD8-PadCN12_10)") (class "Default")
      (node (ref "U1") (pin "CN12_10") (pinfunction "PD8_CN12_10") (pintype "passive"))
    )
    (net (code "192") (name "unconnected-(U1F-PD10-PadCN12_65)") (class "Default")
      (node (ref "U1") (pin "CN12_65") (pinfunction "PD10_CN12_65") (pintype "passive"))
    )
    (net (code "193") (name "unconnected-(U1F-PD11-PadCN12_45)") (class "Default")
      (node (ref "U1") (pin "CN12_45") (pinfunction "PD11_CN12_45") (pintype "passive"))
    )
    (net (code "194") (name "unconnected-(U1F-PD12-PadCN12_43)") (class "Default")
      (node (ref "U1") (pin "CN12_43") (pinfunction "PD12_CN12_43") (pintype "passive"))
    )
    (net (code "195") (name "unconnected-(U1F-PD13-PadCN12_41)") (class "Default")
      (node (ref "U1") (pin "CN12_41") (pinfunction "PD13_CN12_41") (pintype "passive"))
    )
    (net (code "196") (name "unconnected-(U1F-PE10-PadCN12_47)") (class "Default")
      (node (ref "U1") (pin "CN12_47") (pinfunction "PE10_CN12_47") (pintype "passive"))
    )
    (net (code "197") (name "unconnected-(U1F-PE12-PadCN12_49)") (class "Default")
      (node (ref "U1") (pin "CN12_49") (pinfunction "PE12_CN12_49") (pintype "passive"))
    )
    (net (code "198") (name "unconnected-(U1F-PE13-PadCN12_55)") (class "Default")
      (node (ref "U1") (pin "CN12_55") (pinfunction "PE13_CN12_55") (pintype "passive"))
    )
    (net (code "199") (name "unconnected-(U1F-PE14-PadCN12_51)") (class "Default")
      (node (ref "U1") (pin "CN12_51") (pinfunction "PE14_CN12_51") (pintype "passive"))
    )
    (net (code "200") (name "unconnected-(U1F-PE15-PadCN12_53)") (class "Default")
      (node (ref "U1") (pin "CN12_53") (pinfunction "PE15_CN12_53") (pintype "passive"))
    )
    (net (code "201") (name "unconnected-(U1F-PF12-PadCN12_59)") (class "Default")
      (node (ref "U1") (pin "CN12_59") (pinfunction "PF12_CN12_59") (pintype "passive"))
    )
    (net (code "202") (name "unconnected-(U1F-PF13-PadCN12_57)") (class "Default")
      (node (ref "U1") (pin "CN12_57") (pinfunction "PF13_CN12_57") (pintype "passive"))
    )
    (net (code "203") (name "unconnected-(U1F-PG4-PadCN12_69)") (class "Default")
      (node (ref "U1") (pin "CN12_69") (pinfunction "PG4_CN12_69") (pintype "passive"))
    )
    (net (code "204") (name "unconnected-(U1F-PG7-PadCN12_67)") (class "Default")
      (node (ref "U1") (pin "CN12_67") (pinfunction "PG7_CN12_67") (pintype "passive"))
    )
    (net (code "205") (name "unconnected-(U1F-PG14-PadCN12_61)") (class "Default")
      (node (ref "U1") (pin "CN12_61") (pinfunction "PG14_CN12_61") (pintype "passive"))
    )
    (net (code "206") (name "unconnected-(U1F-U5V-PadCN12_8)") (class "Default")
      (node (ref "U1") (pin "CN12_8") (pinfunction "U5V_CN12_8") (pintype "passive"))
    )
  )
)
